# 14_-_MCU.net
KiCad netlist of a schematic drawn in Altium Designer
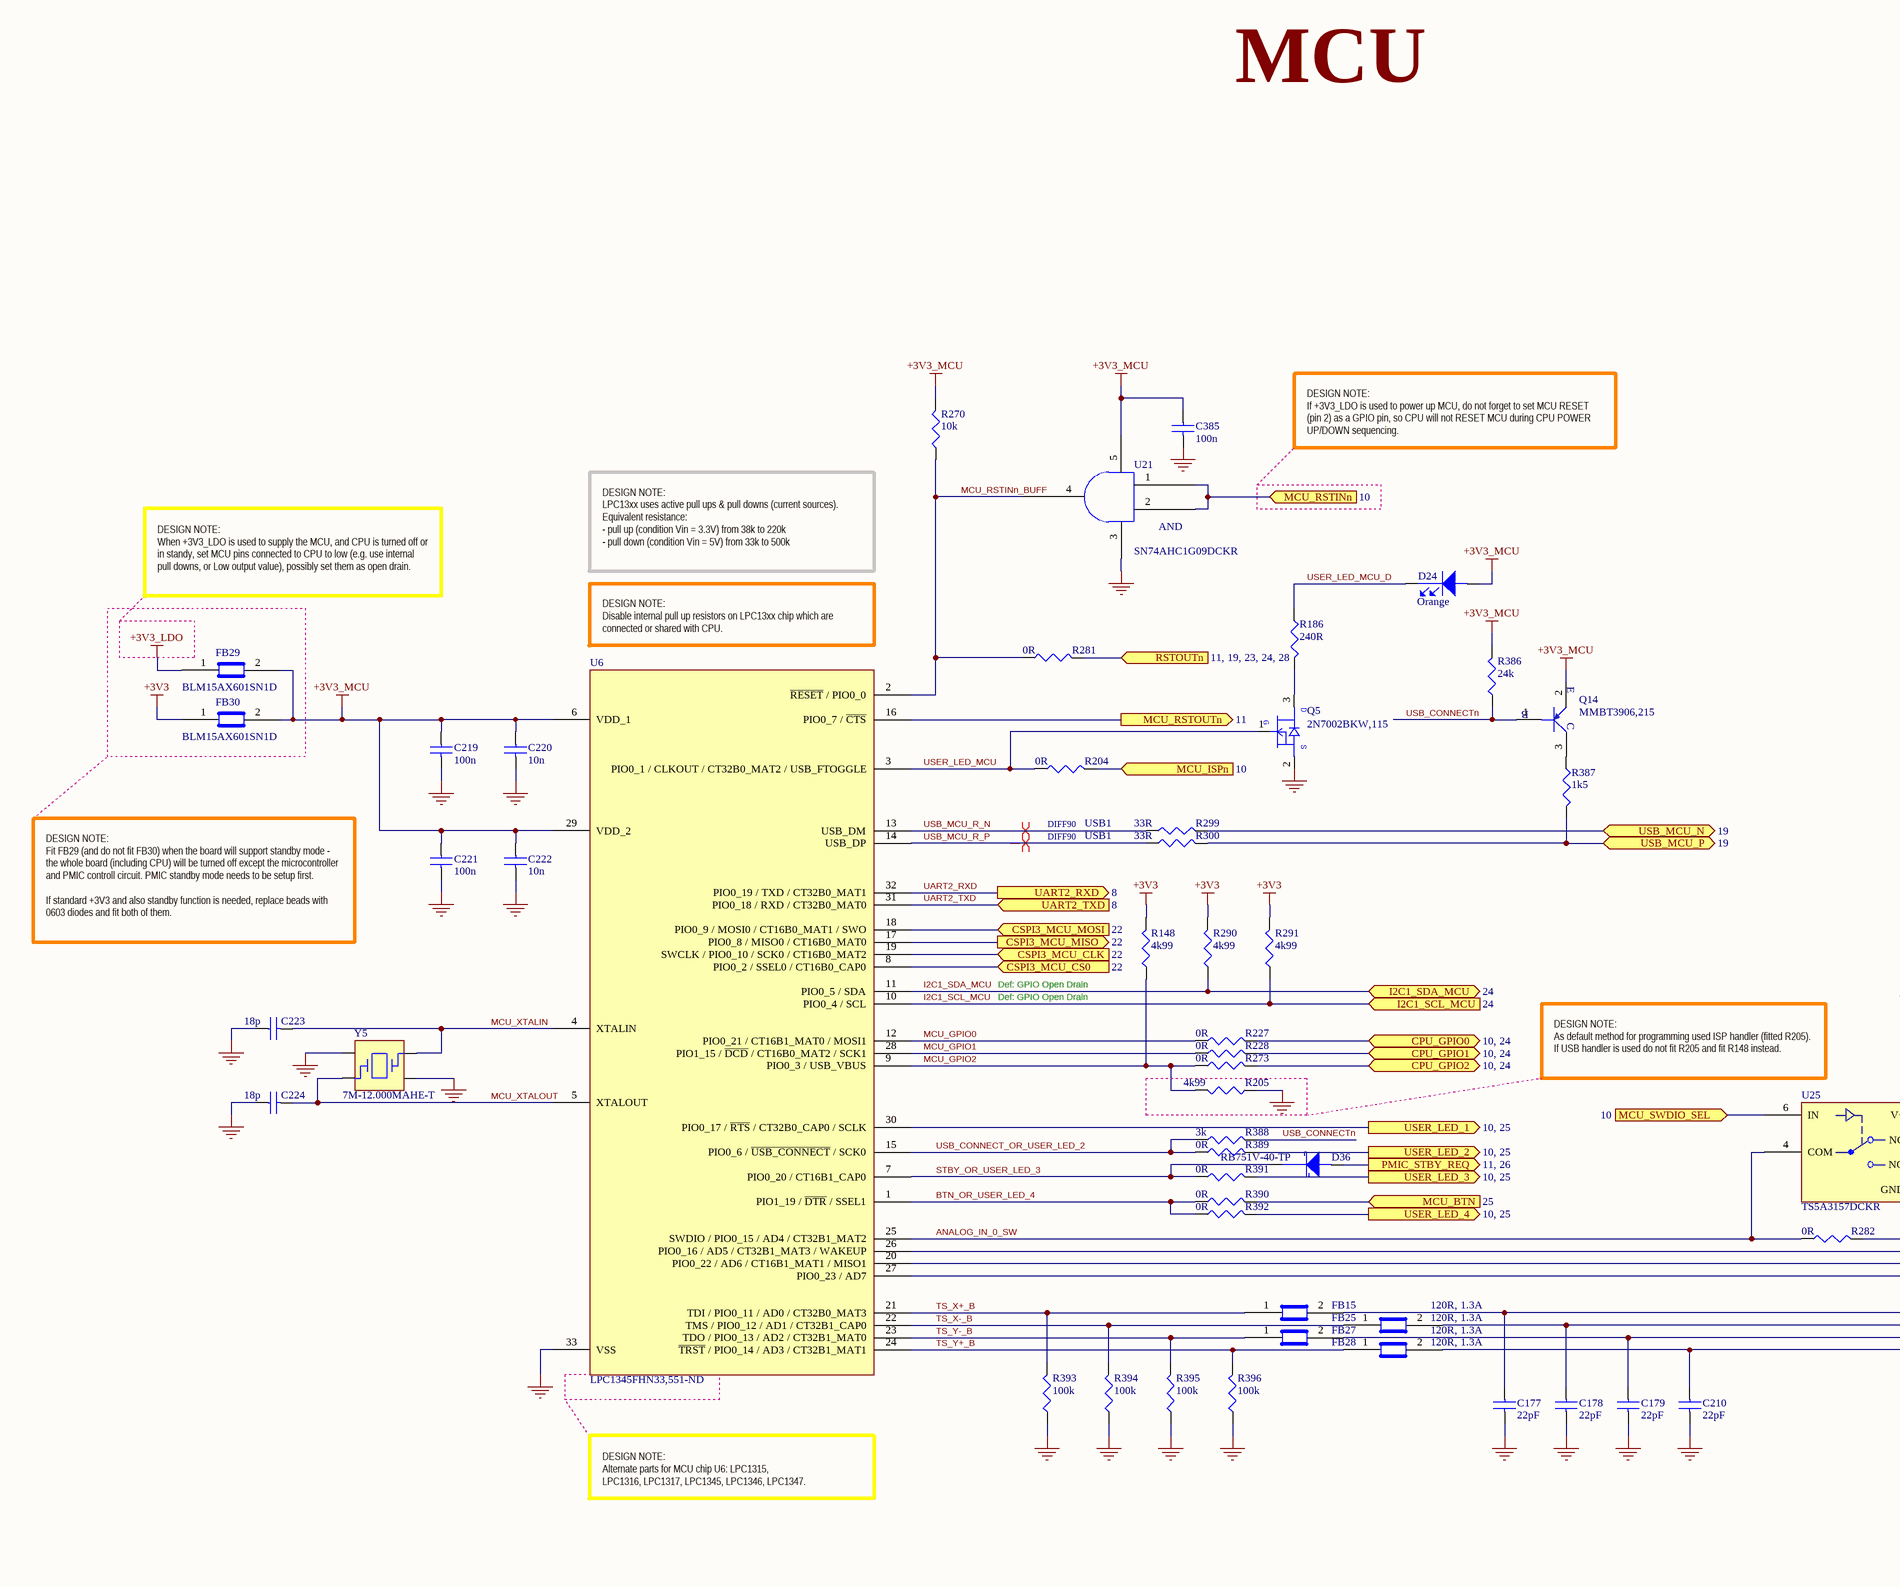
[diagram p0: [14] - MCU.SchDoc, left]
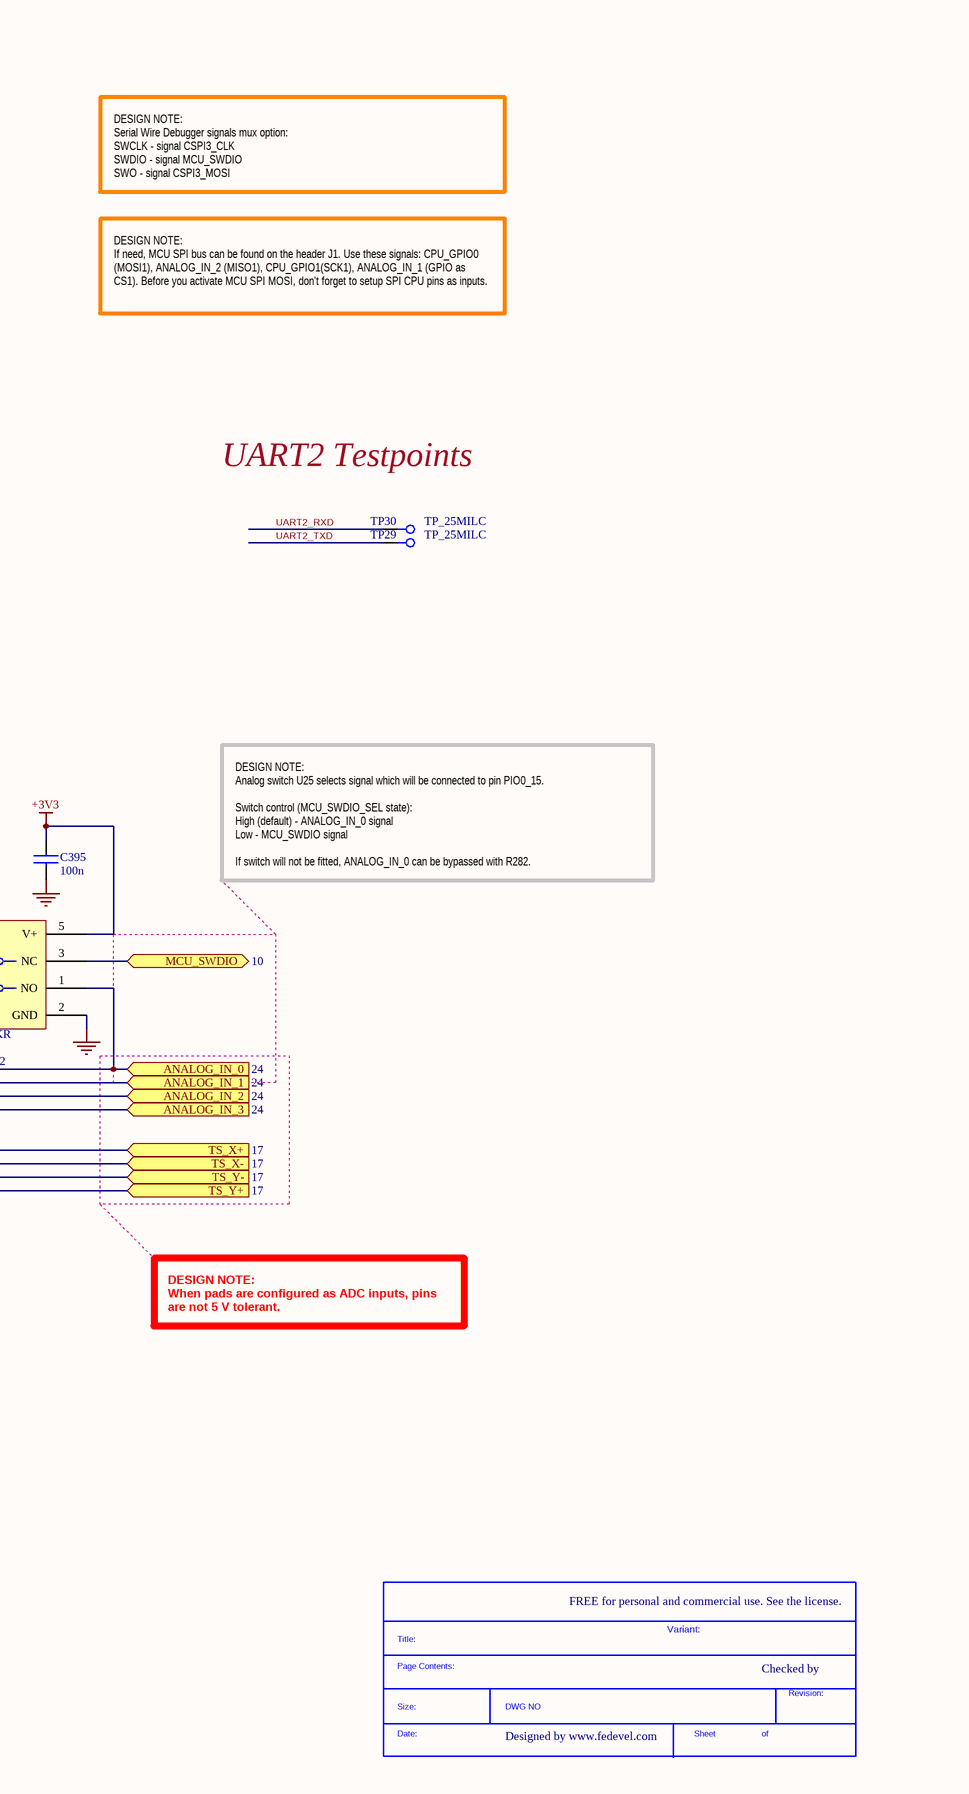
[diagram p1: [14] - MCU.SchDoc, right]

(export (version "E")
  (design (tool "Eeschema 10.0.6"))
  (components
    (comp (ref "C177")
      (value "22pF")
      (footprint "C0402")
      (description "CAP CER 22PF 50V C0G 5% 0402")
      (fields
        (field (name "MANUFACTURER") "TDK Corporation")
        (field (name "MANUFACTURER PART NUMBER") "C1005C0G1H220J")
      )
      (libsource (lib "Integrated_Library_FEDEVEL_APR_2015") (part "C1005C0G1H220J"))
    )
    (comp (ref "C178")
      (value "22pF")
      (footprint "C0402")
      (description "CAP CER 22PF 50V C0G 5% 0402")
      (fields
        (field (name "MANUFACTURER") "TDK Corporation")
        (field (name "MANUFACTURER PART NUMBER") "C1005C0G1H220J")
      )
      (libsource (lib "Integrated_Library_FEDEVEL_APR_2015") (part "C1005C0G1H220J"))
    )
    (comp (ref "C179")
      (value "22pF")
      (footprint "C0402")
      (description "CAP CER 22PF 50V C0G 5% 0402")
      (fields
        (field (name "MANUFACTURER") "TDK Corporation")
        (field (name "MANUFACTURER PART NUMBER") "C1005C0G1H220J")
      )
      (libsource (lib "Integrated_Library_FEDEVEL_APR_2015") (part "C1005C0G1H220J"))
    )
    (comp (ref "C210")
      (value "22pF")
      (footprint "C0402")
      (description "CAP CER 22PF 50V C0G 5% 0402")
      (fields
        (field (name "MANUFACTURER") "TDK Corporation")
        (field (name "MANUFACTURER PART NUMBER") "C1005C0G1H220J")
      )
      (libsource (lib "Integrated_Library_FEDEVEL_APR_2015") (part "C1005C0G1H220J"))
    )
    (comp (ref "C219")
      (value "100n")
      (footprint "C0402")
      (description "CAP CER .10UF 50V X5R 10% 0402")
      (fields
        (field (name "MANUFACTURER") "TDK Corporation")
        (field (name "MANUFACTURER PART NUMBER") "C1005X5R1H104K")
      )
      (libsource (lib "Integrated_Library_FEDEVEL_APR_2015") (part "C1005X5R1H104K"))
    )
    (comp (ref "C220")
      (value "10n")
      (footprint "C0402")
      (description "CAP CER 10000PF 50V 10% X7R 0402")
      (fields
        (field (name "MANUFACTURER") "TDK Corporation")
        (field (name "MANUFACTURER PART NUMBER") "C1005X7R1H103K")
      )
      (libsource (lib "Integrated_Library_FEDEVEL_APR_2015") (part "C1005X7R1H103K"))
    )
    (comp (ref "C221")
      (value "100n")
      (footprint "C0402")
      (description "CAP CER .10UF 50V X5R 10% 0402")
      (fields
        (field (name "MANUFACTURER") "TDK Corporation")
        (field (name "MANUFACTURER PART NUMBER") "C1005X5R1H104K")
      )
      (libsource (lib "Integrated_Library_FEDEVEL_APR_2015") (part "C1005X5R1H104K"))
    )
    (comp (ref "C222")
      (value "10n")
      (footprint "C0402")
      (description "CAP CER 10000PF 50V 10% X7R 0402")
      (fields
        (field (name "MANUFACTURER") "TDK Corporation")
        (field (name "MANUFACTURER PART NUMBER") "C1005X7R1H103K")
      )
      (libsource (lib "Integrated_Library_FEDEVEL_APR_2015") (part "C1005X7R1H103K"))
    )
    (comp (ref "C223")
      (value "18p")
      (footprint "C0402")
      (description "CAP CER 18PF 50V C0G 5% 0402")
      (fields
        (field (name "MANUFACTURER") "TDK Corporation")
        (field (name "MANUFACTURER PART NUMBER") "C1005C0G1H180J")
      )
      (libsource (lib "Integrated_Library_FEDEVEL_APR_2015") (part "C1005C0G1H180J"))
    )
    (comp (ref "C224")
      (value "18p")
      (footprint "C0402")
      (description "CAP CER 18PF 50V C0G 5% 0402")
      (fields
        (field (name "MANUFACTURER") "TDK Corporation")
        (field (name "MANUFACTURER PART NUMBER") "C1005C0G1H180J")
      )
      (libsource (lib "Integrated_Library_FEDEVEL_APR_2015") (part "C1005C0G1H180J"))
    )
    (comp (ref "C385")
      (value "100n")
      (footprint "C0402")
      (description "CAP CER .10UF 50V X5R 10% 0402")
      (fields
        (field (name "MANUFACTURER") "TDK Corporation")
        (field (name "MANUFACTURER PART NUMBER") "C1005X5R1H104K")
      )
      (libsource (lib "Integrated_Library_FEDEVEL_APR_2015") (part "C1005X5R1H104K"))
    )
    (comp (ref "C395")
      (value "100n")
      (footprint "C0402")
      (description "CAP CER .10UF 50V X5R 10% 0402")
      (fields
        (field (name "MANUFACTURER") "TDK Corporation")
        (field (name "MANUFACTURER PART NUMBER") "C1005X5R1H104K")
      )
      (libsource (lib "Integrated_Library_FEDEVEL_APR_2015") (part "C1005X5R1H104K"))
    )
    (comp (ref "D24")
      (value "Orange")
      (footprint "LED_0603")
      (description "LED SMARTLED ORANGE 606NM 0603")
      (fields
        (field (name "MANUFACTURER") "OSRAM Opto Semiconductors Inc")
        (field (name "MANUFACTURER PART NUMBER") "LO L29K-H2K1-24-Z")
      )
      (libsource (lib "Integrated_Library_FEDEVEL_APR_2015") (part "LO L29K-H2K1-24-Z"))
    )
    (comp (ref "D36")
      (value "RB751V-40-TP")
      (footprint "SOD323")
      (description "DIODE SCHTKY 30MA 30V SOD-323")
      (fields (field (name "MANUFACTURER") "Micro Commercial Co"))
      (libsource (lib "Integrated_Library_FEDEVEL_APR_2015") (part "RB751V-40-TP"))
    )
    (comp (ref "FB15")
      (value "120R, 1.3A")
      (footprint "C0402")
      (description "FERRITE CHIP 120 OHM 1300MA 0402")
      (fields
        (field (name "MANUFACTURER") "Murata Electronics North America")
        (field (name "MANUFACTURER PART NUMBER") "BLM15PD121SN1D")
        (field (name ".CHECKED PCB") "MM")
        (field (name ".CHECKED SCH") "MM")
        (field (name ".CREATOR") "MM")
      )
      (libsource (lib "Integrated_Library_FEDEVEL_APR_2015") (part "BLM15PD121SN1D"))
    )
    (comp (ref "FB25")
      (value "120R, 1.3A")
      (footprint "C0402")
      (description "FERRITE CHIP 120 OHM 1300MA 0402")
      (fields
        (field (name "MANUFACTURER") "Murata Electronics North America")
        (field (name "MANUFACTURER PART NUMBER") "BLM15PD121SN1D")
        (field (name ".CHECKED PCB") "MM")
        (field (name ".CHECKED SCH") "MM")
        (field (name ".CREATOR") "MM")
      )
      (libsource (lib "Integrated_Library_FEDEVEL_APR_2015") (part "BLM15PD121SN1D"))
    )
    (comp (ref "FB27")
      (value "120R, 1.3A")
      (footprint "C0402")
      (description "FERRITE CHIP 120 OHM 1300MA 0402")
      (fields
        (field (name "MANUFACTURER") "Murata Electronics North America")
        (field (name "MANUFACTURER PART NUMBER") "BLM15PD121SN1D")
        (field (name ".CHECKED PCB") "MM")
        (field (name ".CHECKED SCH") "MM")
        (field (name ".CREATOR") "MM")
      )
      (libsource (lib "Integrated_Library_FEDEVEL_APR_2015") (part "BLM15PD121SN1D"))
    )
    (comp (ref "FB28")
      (value "120R, 1.3A")
      (footprint "C0402")
      (description "FERRITE CHIP 120 OHM 1300MA 0402")
      (fields
        (field (name "MANUFACTURER") "Murata Electronics North America")
        (field (name "MANUFACTURER PART NUMBER") "BLM15PD121SN1D")
        (field (name ".CHECKED PCB") "MM")
        (field (name ".CHECKED SCH") "MM")
        (field (name ".CREATOR") "MM")
      )
      (libsource (lib "Integrated_Library_FEDEVEL_APR_2015") (part "BLM15PD121SN1D"))
    )
    (comp (ref "FB29")
      (value "BLM15AX601SN1D")
      (footprint "C0402")
      (description "FERRITE CHIP 600 OHM 0402 420mA")
      (fields (field (name "MANUFACTURER") "Murata Electronics North America"))
      (libsource (lib "Integrated_Library_FEDEVEL_APR_2015") (part "BLM15AX601SN1D"))
    )
    (comp (ref "FB30")
      (value "BLM15AX601SN1D")
      (footprint "C0402")
      (description "FERRITE CHIP 600 OHM 0402 420mA")
      (fields (field (name "MANUFACTURER") "Murata Electronics North America"))
      (libsource (lib "Integrated_Library_FEDEVEL_APR_2015") (part "BLM15AX601SN1D"))
    )
    (comp (ref "Q5")
      (value "2N7002BKW,115")
      (footprint "SC70_SOT323")
      (description "MOSFET N-CH 60V 310MA SOT323")
      (fields (field (name "MANUFACTURER") "NXP Semiconductors"))
      (libsource (lib "Integrated_Library_FEDEVEL_APR_2015") (part "2N7002BKW,115"))
    )
    (comp (ref "Q14")
      (value "MMBT3906,215")
      (footprint "SOT-23-3-123")
      (description "TRANS PNP 40V 0.2A SOT23")
      (fields
        (field (name "MANUFACTURER") "NXP Semiconductors")
        (field (name ".CHECKED PCB") "MM")
        (field (name ".CHECKED SCH") "MM")
        (field (name ".CREATOR") "MM")
      )
      (libsource (lib "Integrated_Library_FEDEVEL_APR_2015") (part "MMBT3906,215"))
    )
    (comp (ref "R148")
      (value "4k99")
      (footprint "R0402")
      (description "RES TF 4.99K OHM 1% 1/16W 0402")
      (fields
        (field (name "MANUFACTURER") "Stackpole Electronics Inc")
        (field (name "MANUFACTURER PART NUMBER") "RMCF0402FT4K99")
      )
      (libsource (lib "Integrated_Library_FEDEVEL_APR_2015") (part "RMCF0402FT4K99"))
    )
    (comp (ref "R186")
      (value "240R")
      (footprint "R0402")
      (description "RES TF 240 OHM 1% 0.0625W 0402")
      (fields
        (field (name "MANUFACTURER") "Stackpole Electronics Inc")
        (field (name "MANUFACTURER PART NUMBER") "RMCF0402FT240R")
      )
      (libsource (lib "Integrated_Library_FEDEVEL_APR_2015") (part "RMCF0402FT240R"))
    )
    (comp (ref "R204")
      (value "0R")
      (footprint "R0402")
      (description "RES 0.0 OHM 1/16W 0402 SMD")
      (fields
        (field (name "MANUFACTURER") "Yageo")
        (field (name "MANUFACTURER PART NUMBER") "RC0402JR-070RL")
      )
      (libsource (lib "Integrated_Library_FEDEVEL_APR_2015") (part "RC0402JR-070RL"))
    )
    (comp (ref "R205")
      (value "4k99")
      (footprint "R0402")
      (description "RES TF 4.99K OHM 1% 1/16W 0402")
      (fields
        (field (name "MANUFACTURER") "Stackpole Electronics Inc")
        (field (name "MANUFACTURER PART NUMBER") "RMCF0402FT4K99")
      )
      (libsource (lib "Integrated_Library_FEDEVEL_APR_2015") (part "RMCF0402FT4K99"))
    )
    (comp (ref "R227")
      (value "0R")
      (footprint "R0402")
      (description "RES 0.0 OHM 1/16W 0402 SMD")
      (fields
        (field (name "MANUFACTURER") "Yageo")
        (field (name "MANUFACTURER PART NUMBER") "RC0402JR-070RL")
      )
      (libsource (lib "Integrated_Library_FEDEVEL_APR_2015") (part "RC0402JR-070RL"))
    )
    (comp (ref "R228")
      (value "0R")
      (footprint "R0402")
      (description "RES 0.0 OHM 1/16W 0402 SMD")
      (fields
        (field (name "MANUFACTURER") "Yageo")
        (field (name "MANUFACTURER PART NUMBER") "RC0402JR-070RL")
      )
      (libsource (lib "Integrated_Library_FEDEVEL_APR_2015") (part "RC0402JR-070RL"))
    )
    (comp (ref "R270")
      (value "10k")
      (footprint "R0402")
      (description "RES 10.0K OHM 1/16W 1% 0402 SMD")
      (fields
        (field (name "MANUFACTURER") "Yageo")
        (field (name "MANUFACTURER PART NUMBER") "RC0402FR-0710KL")
      )
      (libsource (lib "Integrated_Library_FEDEVEL_APR_2015") (part "RC0402FR-0710KL"))
    )
    (comp (ref "R273")
      (value "0R")
      (footprint "R0402")
      (description "RES 0.0 OHM 1/16W 0402 SMD")
      (fields
        (field (name "MANUFACTURER") "Yageo")
        (field (name "MANUFACTURER PART NUMBER") "RC0402JR-070RL")
      )
      (libsource (lib "Integrated_Library_FEDEVEL_APR_2015") (part "RC0402JR-070RL"))
    )
    (comp (ref "R281")
      (value "0R")
      (footprint "R0402")
      (description "RES 0.0 OHM 1/16W 0402 SMD")
      (fields
        (field (name "MANUFACTURER") "Yageo")
        (field (name "MANUFACTURER PART NUMBER") "RC0402JR-070RL")
      )
      (libsource (lib "Integrated_Library_FEDEVEL_APR_2015") (part "RC0402JR-070RL"))
    )
    (comp (ref "R282")
      (value "0R")
      (footprint "R0402")
      (description "RES 0.0 OHM 1/16W 0402 SMD")
      (fields
        (field (name "MANUFACTURER") "Yageo")
        (field (name "MANUFACTURER PART NUMBER") "RC0402JR-070RL")
      )
      (libsource (lib "Integrated_Library_FEDEVEL_APR_2015") (part "RC0402JR-070RL"))
    )
    (comp (ref "R290")
      (value "4k99")
      (footprint "R0402")
      (description "RES TF 4.99K OHM 1% 1/16W 0402")
      (fields
        (field (name "MANUFACTURER") "Stackpole Electronics Inc")
        (field (name "MANUFACTURER PART NUMBER") "RMCF0402FT4K99")
      )
      (libsource (lib "Integrated_Library_FEDEVEL_APR_2015") (part "RMCF0402FT4K99"))
    )
    (comp (ref "R291")
      (value "4k99")
      (footprint "R0402")
      (description "RES TF 4.99K OHM 1% 1/16W 0402")
      (fields
        (field (name "MANUFACTURER") "Stackpole Electronics Inc")
        (field (name "MANUFACTURER PART NUMBER") "RMCF0402FT4K99")
      )
      (libsource (lib "Integrated_Library_FEDEVEL_APR_2015") (part "RMCF0402FT4K99"))
    )
    (comp (ref "R299")
      (value "33R")
      (footprint "R0402")
      (description "RES TF 33 OHM 1% 1/16W 0402")
      (fields
        (field (name "MANUFACTURER") "Stackpole Electronics Inc")
        (field (name "MANUFACTURER PART NUMBER") "RMCF0402FT33R0")
      )
      (libsource (lib "Integrated_Library_FEDEVEL_APR_2015") (part "RMCF0402FT33R0"))
    )
    (comp (ref "R300")
      (value "33R")
      (footprint "R0402")
      (description "RES TF 33 OHM 1% 1/16W 0402")
      (fields
        (field (name "MANUFACTURER") "Stackpole Electronics Inc")
        (field (name "MANUFACTURER PART NUMBER") "RMCF0402FT33R0")
      )
      (libsource (lib "Integrated_Library_FEDEVEL_APR_2015") (part "RMCF0402FT33R0"))
    )
    (comp (ref "R386")
      (value "24k")
      (footprint "R0402")
      (description "RES SMD 24K OHM 1% 1/16W 0402")
      (fields
        (field (name "MANUFACTURER") "Yageo")
        (field (name "MANUFACTURER PART NUMBER") "RC0402FR-0724KL")
        (field (name ".CREATOR") "MM")
        (field (name ".CHECKED PCB") "MM")
        (field (name ".CHECKED SCH") "MM")
      )
      (libsource (lib "Integrated_Library_FEDEVEL_APR_2015") (part "RC0402FR-0724KL"))
    )
    (comp (ref "R387")
      (value "1k5")
      (footprint "R0402")
      (description "RES 1.50K OHM 1/16W 1% 0402 SMD")
      (fields
        (field (name "MANUFACTURER") "Yageo")
        (field (name "MANUFACTURER PART NUMBER") "RC0402FR-071K5L")
        (field (name ".CREATOR") "MM")
        (field (name ".CHECKED PCB") "MM")
        (field (name ".CHECKED SCH") "MM")
      )
      (libsource (lib "Integrated_Library_FEDEVEL_APR_2015") (part "RC0402FR-071K5L"))
    )
    (comp (ref "R388")
      (value "3k")
      (footprint "R0402")
      (description "RES 3K OHM 1/16W 1% 0402 SMD")
      (fields
        (field (name "MANUFACTURER") "Yageo")
        (field (name "MANUFACTURER PART NUMBER") "RC0402FR-073KL")
        (field (name ".CREATOR") "MM")
      )
      (libsource (lib "Integrated_Library_FEDEVEL_APR_2015") (part "RC0402FR-073KL"))
    )
    (comp (ref "R389")
      (value "0R")
      (footprint "R0402")
      (description "RES 0.0 OHM 1/16W 0402 SMD")
      (fields
        (field (name "MANUFACTURER") "Yageo")
        (field (name "MANUFACTURER PART NUMBER") "RC0402JR-070RL")
      )
      (libsource (lib "Integrated_Library_FEDEVEL_APR_2015") (part "RC0402JR-070RL"))
    )
    (comp (ref "R390")
      (value "0R")
      (footprint "R0402")
      (description "RES 0.0 OHM 1/16W 0402 SMD")
      (fields
        (field (name "MANUFACTURER") "Yageo")
        (field (name "MANUFACTURER PART NUMBER") "RC0402JR-070RL")
      )
      (libsource (lib "Integrated_Library_FEDEVEL_APR_2015") (part "RC0402JR-070RL"))
    )
    (comp (ref "R391")
      (value "0R")
      (footprint "R0402")
      (description "RES 0.0 OHM 1/16W 0402 SMD")
      (fields
        (field (name "MANUFACTURER") "Yageo")
        (field (name "MANUFACTURER PART NUMBER") "RC0402JR-070RL")
      )
      (libsource (lib "Integrated_Library_FEDEVEL_APR_2015") (part "RC0402JR-070RL"))
    )
    (comp (ref "R392")
      (value "0R")
      (footprint "R0402")
      (description "RES 0.0 OHM 1/16W 0402 SMD")
      (fields
        (field (name "MANUFACTURER") "Yageo")
        (field (name "MANUFACTURER PART NUMBER") "RC0402JR-070RL")
      )
      (libsource (lib "Integrated_Library_FEDEVEL_APR_2015") (part "RC0402JR-070RL"))
    )
    (comp (ref "R393")
      (value "100k")
      (footprint "R0402")
      (description "RES 100K OHM 1/16W 1% 0402 SMD")
      (fields
        (field (name "MANUFACTURER") "Stackpole Electronics Inc")
        (field (name "MANUFACTURER PART NUMBER") "RMCF0402FT100K")
      )
      (libsource (lib "Integrated_Library_FEDEVEL_APR_2015") (part "RMCF0402FT100K"))
    )
    (comp (ref "R394")
      (value "100k")
      (footprint "R0402")
      (description "RES 100K OHM 1/16W 1% 0402 SMD")
      (fields
        (field (name "MANUFACTURER") "Stackpole Electronics Inc")
        (field (name "MANUFACTURER PART NUMBER") "RMCF0402FT100K")
      )
      (libsource (lib "Integrated_Library_FEDEVEL_APR_2015") (part "RMCF0402FT100K"))
    )
    (comp (ref "R395")
      (value "100k")
      (footprint "R0402")
      (description "RES 100K OHM 1/16W 1% 0402 SMD")
      (fields
        (field (name "MANUFACTURER") "Stackpole Electronics Inc")
        (field (name "MANUFACTURER PART NUMBER") "RMCF0402FT100K")
      )
      (libsource (lib "Integrated_Library_FEDEVEL_APR_2015") (part "RMCF0402FT100K"))
    )
    (comp (ref "R396")
      (value "100k")
      (footprint "R0402")
      (description "RES 100K OHM 1/16W 1% 0402 SMD")
      (fields
        (field (name "MANUFACTURER") "Stackpole Electronics Inc")
        (field (name "MANUFACTURER PART NUMBER") "RMCF0402FT100K")
      )
      (libsource (lib "Integrated_Library_FEDEVEL_APR_2015") (part "RMCF0402FT100K"))
    )
    (comp (ref "TP29")
      (value "TP_25MILC")
      (footprint "TP_25C")
      (description "Test Point 25mil")
      (libsource (lib "Integrated_Library_FEDEVEL_APR_2015") (part "TP_25MILC"))
    )
    (comp (ref "TP30")
      (value "TP_25MILC")
      (footprint "TP_25C")
      (description "Test Point 25mil")
      (libsource (lib "Integrated_Library_FEDEVEL_APR_2015") (part "TP_25MILC"))
    )
    (comp (ref "U6")
      (value "LPC1345FHN33,551-ND")
      (footprint "HVQFN33_7x7mm")
      (description "IC MCU ARM 32KB FLASH 32HVQFN")
      (fields
        (field (name "MANUFACTURER") "NXP Semiconductors")
        (field (name "MANUFACTURER PART NUMBER") "LPC1345FHN33,551")
        (field (name ".CHECKED PCB") "MM")
        (field (name ".CHECKED SCH") "MM")
        (field (name ".CREATOR") "MM")
      )
      (libsource (lib "Integrated_Library_FEDEVEL_APR_2015") (part "LPC1345FHN33,551"))
    )
    (comp (ref "U21")
      (value "SN74AHC1G09DCKR")
      (footprint "SC70_5")
      (description "IC GATE AND 1CH 2-INP SC-70-5")
      (fields
        (field (name "MANUFACTURER") "Texas Instruments")
        (field (name ".CREATOR") "MM")
        (field (name ".CHECKED SCH") "MM")
        (field (name ".CHECKED PCB") "RF, used by MM")
      )
      (libsource (lib "Integrated_Library_FEDEVEL_APR_2015") (part "SN74AHC1G09DCKR"))
    )
    (comp (ref "U25")
      (value "TS5A3157DCKR")
      (footprint "SC70_6")
      (description "IC SWITCH SPDT SC70-6")
      (fields
        (field (name "MANUFACTURER") "Texas Instruments")
        (field (name ".CHECKED PCB") "MM")
        (field (name ".CHECKED SCH") "MM")
        (field (name ".CREATOR") "MM")
      )
      (libsource (lib "Integrated_Library_FEDEVEL_APR_2015") (part "TS5A3157DCKR"))
    )
    (comp (ref "Y5")
      (value "7M-12.000MAHE-T")
      (footprint "7M")
      (description "CRYSTAL 12MHZ 12PF SMD")
      (fields
        (field (name "MANUFACTURER") "TXC CORPORATION")
        (field (name ".CREATOR") "MM")
        (field (name ".CHECKED PCB") "MM")
        (field (name ".CHECKED SCH") "MM")
      )
      (libsource (lib "Integrated_Library_FEDEVEL_APR_2015") (part "7M-12.000MAHE-T"))
    )
  )
  (nets
    (net (code "1") (name "+3V3") (class "Default")
      (node (ref "C395") (pin "1") (pinfunction "1_1") (pintype "passive"))
      (node (ref "FB30") (pin "1") (pinfunction "1_1") (pintype "passive"))
      (node (ref "R148") (pin "2") (pinfunction "2_2") (pintype "passive"))
      (node (ref "R290") (pin "2") (pinfunction "2_2") (pintype "passive"))
      (node (ref "R291") (pin "2") (pinfunction "2_2") (pintype "passive"))
      (node (ref "U25") (pin "5") (pinfunction "V+_5") (pintype "passive"))
    )
    (net (code "2") (name "+3V3_LDO") (class "Default")
      (node (ref "FB29") (pin "1") (pinfunction "1_1") (pintype "passive"))
    )
    (net (code "3") (name "+3V3_MCU") (class "Default")
      (node (ref "C219") (pin "1") (pinfunction "1_1") (pintype "passive"))
      (node (ref "C220") (pin "1") (pinfunction "1_1") (pintype "passive"))
      (node (ref "C221") (pin "1") (pinfunction "1_1") (pintype "passive"))
      (node (ref "C222") (pin "1") (pinfunction "1_1") (pintype "passive"))
      (node (ref "C385") (pin "1") (pinfunction "1_1") (pintype "passive"))
      (node (ref "D24") (pin "2") (pinfunction "ANODE_2") (pintype "passive"))
      (node (ref "FB29") (pin "2") (pinfunction "2_2") (pintype "passive"))
      (node (ref "FB30") (pin "2") (pinfunction "2_2") (pintype "passive"))
      (node (ref "Q14") (pin "2") (pinfunction "E_2") (pintype "passive"))
      (node (ref "R270") (pin "2") (pinfunction "2_2") (pintype "passive"))
      (node (ref "R386") (pin "2") (pinfunction "2_2") (pintype "passive"))
      (node (ref "U21") (pin "5") (pinfunction "VCC_5") (pintype "power_in"))
      (node (ref "U6") (pin "29") (pinfunction "VDD_2_29") (pintype "passive"))
      (node (ref "U6") (pin "6") (pinfunction "VDD_1_6") (pintype "passive"))
    )
    (net (code "4") (name "/ANALOG_IN_0") (class "Default")
      (node (ref "R282") (pin "2") (pinfunction "2_2") (pintype "passive"))
      (node (ref "U25") (pin "1") (pinfunction "NO_1") (pintype "passive"))
    )
    (net (code "5") (name "/ANALOG_IN_0_SW") (class "Default")
      (node (ref "R282") (pin "1") (pinfunction "1_1") (pintype "passive"))
      (node (ref "U25") (pin "4") (pinfunction "COM_4") (pintype "passive"))
      (node (ref "U6") (pin "25") (pinfunction "SWDIO_/_PIO0_15_/_AD4_/_CT32B1_MAT2_25") (pintype "passive"))
    )
    (net (code "6") (name "/ANALOG_IN_1") (class "Default")
      (node (ref "U6") (pin "26") (pinfunction "PIO0_16_/_AD5_/_CT32B1_MAT3_/_WAKEUP_26") (pintype "passive"))
    )
    (net (code "7") (name "/ANALOG_IN_2") (class "Default")
      (node (ref "U6") (pin "20") (pinfunction "PIO0_22_/_AD6_/_CT16B1_MAT1_/_MISO1_20") (pintype "passive"))
    )
    (net (code "8") (name "/ANALOG_IN_3") (class "Default")
      (node (ref "U6") (pin "27") (pinfunction "PIO0_23_/_AD7_27") (pintype "passive"))
    )
    (net (code "9") (name "/BTN_OR_USER_LED_4") (class "Default")
      (node (ref "R390") (pin "1") (pinfunction "1_1") (pintype "passive"))
      (node (ref "R392") (pin "1") (pinfunction "1_1") (pintype "passive"))
      (node (ref "U6") (pin "1") (pinfunction "PIO1_19_/_~{DTR}_/_SSEL1_1") (pintype "passive"))
    )
    (net (code "10") (name "/CPU_GPIO0") (class "Default")
      (node (ref "R227") (pin "2") (pinfunction "2_2") (pintype "passive"))
    )
    (net (code "11") (name "/CPU_GPIO1") (class "Default")
      (node (ref "R228") (pin "2") (pinfunction "2_2") (pintype "passive"))
    )
    (net (code "12") (name "/CPU_GPIO2") (class "Default")
      (node (ref "R273") (pin "2") (pinfunction "2_2") (pintype "passive"))
    )
    (net (code "13") (name "/CSPI3_MCU_CLK") (class "Default")
      (node (ref "U6") (pin "19") (pinfunction "SWCLK_/_PIO0_10_/_SCK0_/_CT16B0_MAT2_19") (pintype "passive"))
    )
    (net (code "14") (name "/CSPI3_MCU_CS0") (class "Default")
      (node (ref "U6") (pin "8") (pinfunction "PIO0_2_/_SSEL0_/_CT16B0_CAP0_8") (pintype "passive"))
    )
    (net (code "15") (name "/CSPI3_MCU_MISO") (class "Default")
      (node (ref "U6") (pin "17") (pinfunction "PIO0_8_/_MISO0_/_CT16B0_MAT0_17") (pintype "passive"))
    )
    (net (code "16") (name "/CSPI3_MCU_MOSI") (class "Default")
      (node (ref "U6") (pin "18") (pinfunction "PIO0_9_/_MOSI0_/_CT16B0_MAT1_/_SWO_18") (pintype "passive"))
    )
    (net (code "17") (name "/I2C1_SCL_MCU") (class "Default")
      (node (ref "R291") (pin "1") (pinfunction "1_1") (pintype "passive"))
      (node (ref "U6") (pin "10") (pinfunction "PIO0_4_/_SCL_10") (pintype "passive"))
    )
    (net (code "18") (name "/I2C1_SDA_MCU") (class "Default")
      (node (ref "R290") (pin "1") (pinfunction "1_1") (pintype "passive"))
      (node (ref "U6") (pin "11") (pinfunction "PIO0_5_/_SDA_11") (pintype "passive"))
    )
    (net (code "19") (name "/MCU_BTN") (class "Default")
      (node (ref "R390") (pin "2") (pinfunction "2_2") (pintype "passive"))
    )
    (net (code "20") (name "/MCU_GPIO0") (class "Default")
      (node (ref "R227") (pin "1") (pinfunction "1_1") (pintype "passive"))
      (node (ref "U6") (pin "12") (pinfunction "PIO0_21_/_CT16B1_MAT0_/_MOSI1_12") (pintype "passive"))
    )
    (net (code "21") (name "/MCU_GPIO1") (class "Default")
      (node (ref "R228") (pin "1") (pinfunction "1_1") (pintype "passive"))
      (node (ref "U6") (pin "28") (pinfunction "PIO1_15_/_~{DCD}_/_CT16B0_MAT2_/_SCK1_28") (pintype "passive"))
    )
    (net (code "22") (name "/MCU_GPIO2") (class "Default")
      (node (ref "R148") (pin "1") (pinfunction "1_1") (pintype "passive"))
      (node (ref "R205") (pin "2") (pinfunction "2_2") (pintype "passive"))
      (node (ref "R273") (pin "1") (pinfunction "1_1") (pintype "passive"))
      (node (ref "U6") (pin "9") (pinfunction "PIO0_3_/_USB_VBUS_9") (pintype "passive"))
    )
    (net (code "23") (name "/MCU_ISPn") (class "Default")
      (node (ref "R204") (pin "2") (pinfunction "2_2") (pintype "passive"))
    )
    (net (code "24") (name "/MCU_RSTINn") (class "Default")
      (node (ref "U21") (pin "1") (pinfunction "A_1") (pintype "passive"))
      (node (ref "U21") (pin "2") (pinfunction "B_2") (pintype "passive"))
    )
    (net (code "25") (name "/MCU_RSTINn_BUFF") (class "Default")
      (node (ref "R270") (pin "1") (pinfunction "1_1") (pintype "passive"))
      (node (ref "R281") (pin "1") (pinfunction "1_1") (pintype "passive"))
      (node (ref "U21") (pin "4") (pinfunction "Y_4") (pintype "passive"))
      (node (ref "U6") (pin "2") (pinfunction "~{RESET}_/_PIO0_0_2") (pintype "passive"))
    )
    (net (code "26") (name "/MCU_RSTOUTn") (class "Default")
      (node (ref "U6") (pin "16") (pinfunction "PIO0_7_/_~{CTS}_16") (pintype "passive"))
    )
    (net (code "27") (name "/MCU_SWDIO") (class "Default")
      (node (ref "U25") (pin "3") (pinfunction "NC_3") (pintype "passive"))
    )
    (net (code "28") (name "/MCU_SWDIO_SEL") (class "Default")
      (node (ref "U25") (pin "6") (pinfunction "IN_6") (pintype "passive"))
    )
    (net (code "29") (name "/MCU_XTALIN") (class "Default")
      (node (ref "C223") (pin "2") (pinfunction "2_2") (pintype "passive"))
      (node (ref "U6") (pin "4") (pinfunction "XTALIN_4") (pintype "passive"))
      (node (ref "Y5") (pin "1") (pinfunction "1_1") (pintype "passive"))
    )
    (net (code "30") (name "/MCU_XTALOUT") (class "Default")
      (node (ref "C224") (pin "2") (pinfunction "2_2") (pintype "passive"))
      (node (ref "U6") (pin "5") (pinfunction "XTALOUT_5") (pintype "passive"))
      (node (ref "Y5") (pin "3") (pinfunction "3_3") (pintype "passive"))
    )
    (net (code "31") (name "/PMIC_STBY_REQ") (class "Default")
      (node (ref "D36") (pin "2") (pinfunction "ANODE_2") (pintype "passive"))
    )
    (net (code "32") (name "/RSTOUTn") (class "Default")
      (node (ref "R281") (pin "2") (pinfunction "2_2") (pintype "passive"))
    )
    (net (code "33") (name "/STBY_OR_USER_LED_3") (class "Default")
      (node (ref "D36") (pin "1") (pinfunction "cathode_1") (pintype "passive"))
      (node (ref "R391") (pin "1") (pinfunction "1_1") (pintype "passive"))
      (node (ref "U6") (pin "7") (pinfunction "PIO0_20_/_CT16B1_CAP0_7") (pintype "passive"))
    )
    (net (code "34") (name "/TS_X+") (class "Default")
      (node (ref "C177") (pin "1") (pinfunction "1_1") (pintype "passive"))
      (node (ref "FB15") (pin "2") (pinfunction "2_2") (pintype "passive"))
    )
    (net (code "35") (name "/TS_X+_B") (class "Default")
      (node (ref "FB15") (pin "1") (pinfunction "1_1") (pintype "passive"))
      (node (ref "R393") (pin "2") (pinfunction "2_2") (pintype "passive"))
      (node (ref "U6") (pin "21") (pinfunction "TDI_/_PIO0_11_/_AD0_/_CT32B0_MAT3_21") (pintype "passive"))
    )
    (net (code "36") (name "/TS_X-") (class "Default")
      (node (ref "C178") (pin "1") (pinfunction "1_1") (pintype "passive"))
      (node (ref "FB25") (pin "2") (pinfunction "2_2") (pintype "passive"))
    )
    (net (code "37") (name "/TS_X-_B") (class "Default")
      (node (ref "FB25") (pin "1") (pinfunction "1_1") (pintype "passive"))
      (node (ref "R394") (pin "2") (pinfunction "2_2") (pintype "passive"))
      (node (ref "U6") (pin "22") (pinfunction "TMS_/_PIO0_12_/_AD1_/_CT32B1_CAP0_22") (pintype "passive"))
    )
    (net (code "38") (name "/TS_Y+") (class "Default")
      (node (ref "C210") (pin "1") (pinfunction "1_1") (pintype "passive"))
      (node (ref "FB28") (pin "2") (pinfunction "2_2") (pintype "passive"))
    )
    (net (code "39") (name "/TS_Y+_B") (class "Default")
      (node (ref "FB28") (pin "1") (pinfunction "1_1") (pintype "passive"))
      (node (ref "R396") (pin "2") (pinfunction "2_2") (pintype "passive"))
      (node (ref "U6") (pin "24") (pinfunction "~{TRST}_/_PIO0_14_/_AD3_/_CT32B1_MAT1_24") (pintype "passive"))
    )
    (net (code "40") (name "/TS_Y-") (class "Default")
      (node (ref "C179") (pin "1") (pinfunction "1_1") (pintype "passive"))
      (node (ref "FB27") (pin "2") (pinfunction "2_2") (pintype "passive"))
    )
    (net (code "41") (name "/TS_Y-_B") (class "Default")
      (node (ref "FB27") (pin "1") (pinfunction "1_1") (pintype "passive"))
      (node (ref "R395") (pin "2") (pinfunction "2_2") (pintype "passive"))
      (node (ref "U6") (pin "23") (pinfunction "TDO_/_PIO0_13_/_AD2_/_CT32B1_MAT0_23") (pintype "passive"))
    )
    (net (code "42") (name "/UART2_RXD") (class "Default")
      (node (ref "TP30") (pin "1") (pinfunction "1_1") (pintype "passive"))
      (node (ref "U6") (pin "32") (pinfunction "PIO0_19_/_TXD_/_CT32B0_MAT1_32") (pintype "passive"))
    )
    (net (code "43") (name "/UART2_TXD") (class "Default")
      (node (ref "TP29") (pin "1") (pinfunction "1_1") (pintype "passive"))
      (node (ref "U6") (pin "31") (pinfunction "PIO0_18_/_RXD_/_CT32B0_MAT0_31") (pintype "passive"))
    )
    (net (code "44") (name "/USB_CONNECT_OR_USER_LED_2") (class "Default")
      (node (ref "R388") (pin "1") (pinfunction "1_1") (pintype "passive"))
      (node (ref "R389") (pin "1") (pinfunction "1_1") (pintype "passive"))
      (node (ref "U6") (pin "15") (pinfunction "PIO0_6_/_~{USB_CONNECT}_/_SCK0_15") (pintype "passive"))
    )
    (net (code "45") (name "/USB_CONNECTn") (class "Default")
      (node (ref "Q14") (pin "1") (pinfunction "B_1") (pintype "passive"))
      (node (ref "R386") (pin "1") (pinfunction "1_1") (pintype "passive"))
      (node (ref "R388") (pin "2") (pinfunction "2_2") (pintype "passive"))
    )
    (net (code "46") (name "/USB_MCU_N") (class "Default")
      (node (ref "R299") (pin "2") (pinfunction "2_2") (pintype "passive"))
    )
    (net (code "47") (name "/USB_MCU_P") (class "Default")
      (node (ref "R300") (pin "2") (pinfunction "2_2") (pintype "passive"))
      (node (ref "R387") (pin "2") (pinfunction "2_2") (pintype "passive"))
    )
    (net (code "48") (name "/USB_MCU_R_N") (class "Default")
      (node (ref "R299") (pin "1") (pinfunction "1_1") (pintype "passive"))
      (node (ref "U6") (pin "13") (pinfunction "USB_DM_13") (pintype "passive"))
    )
    (net (code "49") (name "/USB_MCU_R_P") (class "Default")
      (node (ref "R300") (pin "1") (pinfunction "1_1") (pintype "passive"))
      (node (ref "U6") (pin "14") (pinfunction "USB_DP_14") (pintype "passive"))
    )
    (net (code "50") (name "/USER_LED_1") (class "Default")
      (node (ref "U6") (pin "30") (pinfunction "PIO0_17_/_~{RTS}_/_CT32B0_CAP0_/_SCLK_30") (pintype "passive"))
    )
    (net (code "51") (name "/USER_LED_2") (class "Default")
      (node (ref "R389") (pin "2") (pinfunction "2_2") (pintype "passive"))
    )
    (net (code "52") (name "/USER_LED_3") (class "Default")
      (node (ref "R391") (pin "2") (pinfunction "2_2") (pintype "passive"))
    )
    (net (code "53") (name "/USER_LED_4") (class "Default")
      (node (ref "R392") (pin "2") (pinfunction "2_2") (pintype "passive"))
    )
    (net (code "54") (name "/USER_LED_MCU") (class "Default")
      (node (ref "Q5") (pin "1") (pinfunction "GATE_1") (pintype "passive"))
      (node (ref "R204") (pin "1") (pinfunction "1_1") (pintype "passive"))
      (node (ref "U6") (pin "3") (pinfunction "PIO0_1_/_CLKOUT_/_CT32B0_MAT2_/_USB_FTOGGLE_3") (pintype "passive"))
    )
    (net (code "55") (name "/USER_LED_MCU_D") (class "Default")
      (node (ref "D24") (pin "1") (pinfunction "cathode_1") (pintype "passive"))
      (node (ref "R186") (pin "1") (pinfunction "1_1") (pintype "passive"))
    )
    (net (code "56") (name "GND") (class "Default")
      (node (ref "C177") (pin "2") (pinfunction "2_2") (pintype "passive"))
      (node (ref "C178") (pin "2") (pinfunction "2_2") (pintype "passive"))
      (node (ref "C179") (pin "2") (pinfunction "2_2") (pintype "passive"))
      (node (ref "C210") (pin "2") (pinfunction "2_2") (pintype "passive"))
      (node (ref "C219") (pin "2") (pinfunction "2_2") (pintype "passive"))
      (node (ref "C220") (pin "2") (pinfunction "2_2") (pintype "passive"))
      (node (ref "C221") (pin "2") (pinfunction "2_2") (pintype "passive"))
      (node (ref "C222") (pin "2") (pinfunction "2_2") (pintype "passive"))
      (node (ref "C223") (pin "1") (pinfunction "1_1") (pintype "passive"))
      (node (ref "C224") (pin "1") (pinfunction "1_1") (pintype "passive"))
      (node (ref "C385") (pin "2") (pinfunction "2_2") (pintype "passive"))
      (node (ref "C395") (pin "2") (pinfunction "2_2") (pintype "passive"))
      (node (ref "Q5") (pin "2") (pinfunction "SOURCE_2") (pintype "passive"))
      (node (ref "R205") (pin "1") (pinfunction "1_1") (pintype "passive"))
      (node (ref "R393") (pin "1") (pinfunction "1_1") (pintype "passive"))
      (node (ref "R394") (pin "1") (pinfunction "1_1") (pintype "passive"))
      (node (ref "R395") (pin "1") (pinfunction "1_1") (pintype "passive"))
      (node (ref "R396") (pin "1") (pinfunction "1_1") (pintype "passive"))
      (node (ref "U21") (pin "3") (pinfunction "GND_3") (pintype "power_in"))
      (node (ref "U25") (pin "2") (pinfunction "GND_2") (pintype "passive"))
      (node (ref "U6") (pin "33") (pinfunction "VSS_33") (pintype "passive"))
      (node (ref "Y5") (pin "2") (pinfunction "2_2") (pintype "passive"))
      (node (ref "Y5") (pin "4") (pinfunction "4_4") (pintype "passive"))
    )
    (net (code "57") (name "Net-(Q5-DRAIN)") (class "Default")
      (node (ref "Q5") (pin "3") (pinfunction "DRAIN_3") (pintype "passive"))
      (node (ref "R186") (pin "2") (pinfunction "2_2") (pintype "passive"))
    )
    (net (code "58") (name "Net-(Q14-C)") (class "Default")
      (node (ref "Q14") (pin "3") (pinfunction "C_3") (pintype "passive"))
      (node (ref "R387") (pin "1") (pinfunction "1_1") (pintype "passive"))
    )
  )
)
